# KAMERA_ALPHA.net
KiCad netlist of a schematic drawn in EAGLE
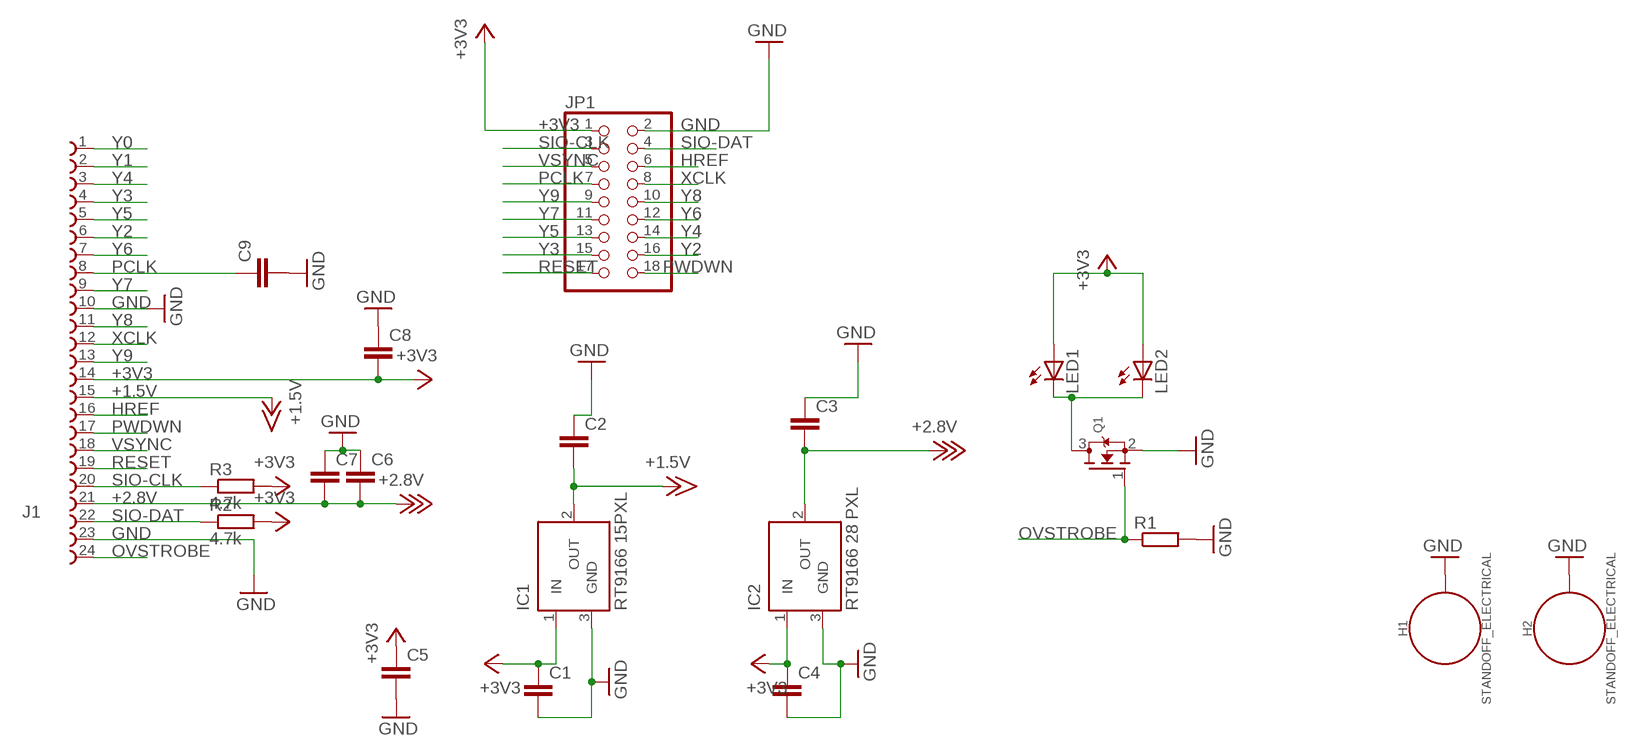
[diagram p0: schematic, sheet 1]

(export (version "E")
  (design (tool "Eeschema 10.0.6"))
  (components
    (comp (ref "C1")
      (value "C-EUC0805K")
      (footprint "eagle-import:C0805K")
      (libsource (lib "eagle-import") (part "C-EUC0805K"))
    )
    (comp (ref "C2")
      (value "C-EUC0805K")
      (footprint "eagle-import:C0805K")
      (libsource (lib "eagle-import") (part "C-EUC0805K"))
    )
    (comp (ref "C3")
      (value "C-EUC0805K")
      (footprint "eagle-import:C0805K")
      (libsource (lib "eagle-import") (part "C-EUC0805K"))
    )
    (comp (ref "C4")
      (value "C-EUC0805K")
      (footprint "eagle-import:C0805K")
      (libsource (lib "eagle-import") (part "C-EUC0805K"))
    )
    (comp (ref "C5")
      (value "C-EUC0805K")
      (footprint "eagle-import:C0805K")
      (libsource (lib "eagle-import") (part "C-EUC0805K"))
    )
    (comp (ref "C6")
      (value "C-EUC0805K")
      (footprint "eagle-import:C0805K")
      (libsource (lib "eagle-import") (part "C-EUC0805K"))
    )
    (comp (ref "C7")
      (value "C-EUC0805K")
      (footprint "eagle-import:C0805K")
      (libsource (lib "eagle-import") (part "C-EUC0805K"))
    )
    (comp (ref "C8")
      (value "C-EUC0805K")
      (footprint "eagle-import:C0805K")
      (libsource (lib "eagle-import") (part "C-EUC0805K"))
    )
    (comp (ref "C9")
      (value "C-EUC0805K")
      (footprint "eagle-import:C0805K")
      (libsource (lib "eagle-import") (part "C-EUC0805K"))
    )
    (comp (ref "H1")
      (value "STANDOFF_ELECTRICAL")
      (footprint "eagle-import:STANDOFF-ELECTRICAL")
      (libsource (lib "eagle-import") (part "STANDOFF_ELECTRICAL"))
    )
    (comp (ref "H2")
      (value "STANDOFF_ELECTRICAL")
      (footprint "eagle-import:STANDOFF-ELECTRICAL")
      (libsource (lib "eagle-import") (part "STANDOFF_ELECTRICAL"))
    )
    (comp (ref "IC1")
      (value "RT9166 15PXL")
      (footprint "eagle-import:SOT23")
      (fields (field (name "MF") "MAXIM") (field (name "MPN") "MAX6520EUR-T"))
      (libsource (lib "eagle-import") (part "MAX6520"))
    )
    (comp (ref "IC2")
      (value "RT9166 28 PXL")
      (footprint "eagle-import:SOT23")
      (fields (field (name "MF") "MAXIM") (field (name "MPN") "MAX6520EUR-T"))
      (libsource (lib "eagle-import") (part "MAX6520"))
    )
    (comp (ref "J1")
      (value "68712414022")
      (footprint "eagle-import:68712414022")
      (libsource (lib "eagle-import") (part "68712414022"))
    )
    (comp (ref "JP1")
      (value "PINHD-2X9")
      (footprint "eagle-import:2X09")
      (libsource (lib "eagle-import") (part "PINHD-2X9"))
    )
    (comp (ref "LED1")
      (value "LEDCHIPLED_0805")
      (footprint "eagle-import:CHIPLED_0805")
      (libsource (lib "eagle-import") (part "LEDCHIPLED_0805"))
    )
    (comp (ref "LED2")
      (value "LEDCHIPLED_0805")
      (footprint "eagle-import:CHIPLED_0805")
      (libsource (lib "eagle-import") (part "LEDCHIPLED_0805"))
    )
    (comp (ref "Q1")
      (value "MOSFET-NREFLOW")
      (footprint "eagle-import:SOT23")
      (libsource (lib "eagle-import") (part "MOSFET-NREFLOW"))
    )
    (comp (ref "R1")
      (value "R-EU_R0805")
      (footprint "eagle-import:R0805")
      (libsource (lib "eagle-import") (part "R-EU_R0805"))
    )
    (comp (ref "R2")
      (value "4.7k")
      (footprint "eagle-import:R0805")
      (libsource (lib "eagle-import") (part "R-EU_R0805"))
    )
    (comp (ref "R3")
      (value "4.7k")
      (footprint "eagle-import:R0805")
      (libsource (lib "eagle-import") (part "R-EU_R0805"))
    )
  )
  (nets
    (net (code "1") (name "+1.5V") (class "Default")
      (node (ref "C2") (pin "2") (pinfunction "2_2") (pintype "passive"))
      (node (ref "IC1") (pin "2") (pinfunction "OUT_2") (pintype "output"))
      (node (ref "J1") (pin "15") (pinfunction "10_15") (pintype "passive"))
    )
    (net (code "2") (name "+2.8V") (class "Default")
      (node (ref "C3") (pin "2") (pinfunction "2_2") (pintype "passive"))
      (node (ref "C6") (pin "2") (pinfunction "2_2") (pintype "passive"))
      (node (ref "C7") (pin "2") (pinfunction "2_2") (pintype "passive"))
      (node (ref "IC2") (pin "2") (pinfunction "OUT_2") (pintype "output"))
      (node (ref "J1") (pin "21") (pinfunction "4_21") (pintype "passive"))
    )
    (net (code "3") (name "+3V3") (class "Default")
      (node (ref "C1") (pin "1") (pinfunction "1_1") (pintype "passive"))
      (node (ref "C4") (pin "1") (pinfunction "1_1") (pintype "passive"))
      (node (ref "C5") (pin "1") (pinfunction "1_1") (pintype "passive"))
      (node (ref "C8") (pin "2") (pinfunction "2_2") (pintype "passive"))
      (node (ref "IC1") (pin "1") (pinfunction "IN_1") (pintype "input"))
      (node (ref "IC2") (pin "1") (pinfunction "IN_1") (pintype "input"))
      (node (ref "J1") (pin "14") (pinfunction "11_14") (pintype "passive"))
      (node (ref "JP1") (pin "1") (pinfunction "1_1") (pintype "passive"))
      (node (ref "LED1") (pin "A") (pinfunction "A_A") (pintype "passive"))
      (node (ref "LED2") (pin "A") (pinfunction "A_A") (pintype "passive"))
      (node (ref "R2") (pin "2") (pinfunction "2_2") (pintype "passive"))
      (node (ref "R3") (pin "2") (pinfunction "2_2") (pintype "passive"))
    )
    (net (code "4") (name "/HREF") (class "Default")
      (node (ref "J1") (pin "16") (pinfunction "9_16") (pintype "passive"))
      (node (ref "JP1") (pin "6") (pinfunction "6_6") (pintype "passive"))
    )
    (net (code "5") (name "/OVSTROBE") (class "Default")
      (node (ref "J1") (pin "24") (pinfunction "1_24") (pintype "passive"))
      (node (ref "Q1") (pin "1") (pinfunction "G_1") (pintype "bidirectional"))
      (node (ref "R1") (pin "1") (pinfunction "1_1") (pintype "passive"))
    )
    (net (code "6") (name "/PCLK") (class "Default")
      (node (ref "C9") (pin "1") (pinfunction "1_1") (pintype "passive"))
      (node (ref "J1") (pin "8") (pinfunction "17_8") (pintype "passive"))
      (node (ref "JP1") (pin "7") (pinfunction "7_7") (pintype "passive"))
    )
    (net (code "7") (name "/PWDWN") (class "Default")
      (node (ref "J1") (pin "17") (pinfunction "8_17") (pintype "passive"))
      (node (ref "JP1") (pin "18") (pinfunction "18_18") (pintype "passive"))
    )
    (net (code "8") (name "/RESET") (class "Default")
      (node (ref "J1") (pin "19") (pinfunction "6_19") (pintype "passive"))
      (node (ref "JP1") (pin "17") (pinfunction "17_17") (pintype "passive"))
    )
    (net (code "9") (name "/SIO-CLK") (class "Default")
      (node (ref "J1") (pin "20") (pinfunction "5_20") (pintype "passive"))
      (node (ref "JP1") (pin "3") (pinfunction "3_3") (pintype "passive"))
      (node (ref "R3") (pin "1") (pinfunction "1_1") (pintype "passive"))
    )
    (net (code "10") (name "/SIO-DAT") (class "Default")
      (node (ref "J1") (pin "22") (pinfunction "3_22") (pintype "passive"))
      (node (ref "JP1") (pin "4") (pinfunction "4_4") (pintype "passive"))
      (node (ref "R2") (pin "1") (pinfunction "1_1") (pintype "passive"))
    )
    (net (code "11") (name "/VSYNC") (class "Default")
      (node (ref "J1") (pin "18") (pinfunction "7_18") (pintype "passive"))
      (node (ref "JP1") (pin "5") (pinfunction "5_5") (pintype "passive"))
    )
    (net (code "12") (name "/XCLK") (class "Default")
      (node (ref "J1") (pin "12") (pinfunction "13_12") (pintype "passive"))
      (node (ref "JP1") (pin "8") (pinfunction "8_8") (pintype "passive"))
    )
    (net (code "13") (name "/Y0") (class "Default")
      (node (ref "J1") (pin "1") (pinfunction "24_1") (pintype "passive"))
    )
    (net (code "14") (name "/Y1") (class "Default")
      (node (ref "J1") (pin "2") (pinfunction "23_2") (pintype "passive"))
    )
    (net (code "15") (name "/Y2") (class "Default")
      (node (ref "J1") (pin "6") (pinfunction "19_6") (pintype "passive"))
      (node (ref "JP1") (pin "16") (pinfunction "16_16") (pintype "passive"))
    )
    (net (code "16") (name "/Y3") (class "Default")
      (node (ref "J1") (pin "4") (pinfunction "21_4") (pintype "passive"))
      (node (ref "JP1") (pin "15") (pinfunction "15_15") (pintype "passive"))
    )
    (net (code "17") (name "/Y4") (class "Default")
      (node (ref "J1") (pin "3") (pinfunction "22_3") (pintype "passive"))
      (node (ref "JP1") (pin "14") (pinfunction "14_14") (pintype "passive"))
    )
    (net (code "18") (name "/Y5") (class "Default")
      (node (ref "J1") (pin "5") (pinfunction "20_5") (pintype "passive"))
      (node (ref "JP1") (pin "13") (pinfunction "13_13") (pintype "passive"))
    )
    (net (code "19") (name "/Y6") (class "Default")
      (node (ref "J1") (pin "7") (pinfunction "18_7") (pintype "passive"))
      (node (ref "JP1") (pin "12") (pinfunction "12_12") (pintype "passive"))
    )
    (net (code "20") (name "/Y7") (class "Default")
      (node (ref "J1") (pin "9") (pinfunction "16_9") (pintype "passive"))
      (node (ref "JP1") (pin "11") (pinfunction "11_11") (pintype "passive"))
    )
    (net (code "21") (name "/Y8") (class "Default")
      (node (ref "J1") (pin "11") (pinfunction "14_11") (pintype "passive"))
      (node (ref "JP1") (pin "10") (pinfunction "10_10") (pintype "passive"))
    )
    (net (code "22") (name "/Y9") (class "Default")
      (node (ref "J1") (pin "13") (pinfunction "12_13") (pintype "passive"))
      (node (ref "JP1") (pin "9") (pinfunction "9_9") (pintype "passive"))
    )
    (net (code "23") (name "GND") (class "Default")
      (node (ref "C1") (pin "2") (pinfunction "2_2") (pintype "passive"))
      (node (ref "C2") (pin "1") (pinfunction "1_1") (pintype "passive"))
      (node (ref "C3") (pin "1") (pinfunction "1_1") (pintype "passive"))
      (node (ref "C4") (pin "2") (pinfunction "2_2") (pintype "passive"))
      (node (ref "C5") (pin "2") (pinfunction "2_2") (pintype "passive"))
      (node (ref "C6") (pin "1") (pinfunction "1_1") (pintype "passive"))
      (node (ref "C7") (pin "1") (pinfunction "1_1") (pintype "passive"))
      (node (ref "C8") (pin "1") (pinfunction "1_1") (pintype "passive"))
      (node (ref "C9") (pin "2") (pinfunction "2_2") (pintype "passive"))
      (node (ref "H1") (pin "P1") (pinfunction "P$1_P1") (pintype "bidirectional"))
      (node (ref "H2") (pin "P1") (pinfunction "P$1_P1") (pintype "bidirectional"))
      (node (ref "IC1") (pin "3") (pinfunction "GND_3") (pintype "power_in"))
      (node (ref "IC2") (pin "3") (pinfunction "GND_3") (pintype "power_in"))
      (node (ref "J1") (pin "10") (pinfunction "15_10") (pintype "passive"))
      (node (ref "J1") (pin "23") (pinfunction "2_23") (pintype "passive"))
      (node (ref "JP1") (pin "2") (pinfunction "2_2") (pintype "passive"))
      (node (ref "Q1") (pin "2") (pinfunction "S_2") (pintype "bidirectional"))
      (node (ref "R1") (pin "2") (pinfunction "2_2") (pintype "passive"))
    )
    (net (code "24") (name "Net-(Q1-D)") (class "Default")
      (node (ref "LED1") (pin "C") (pinfunction "C_C") (pintype "passive"))
      (node (ref "LED2") (pin "C") (pinfunction "C_C") (pintype "passive"))
      (node (ref "Q1") (pin "3") (pinfunction "D_3") (pintype "bidirectional"))
    )
  )
)
